# LNA_copy.net
KiCad netlist of a schematic drawn in EAGLE
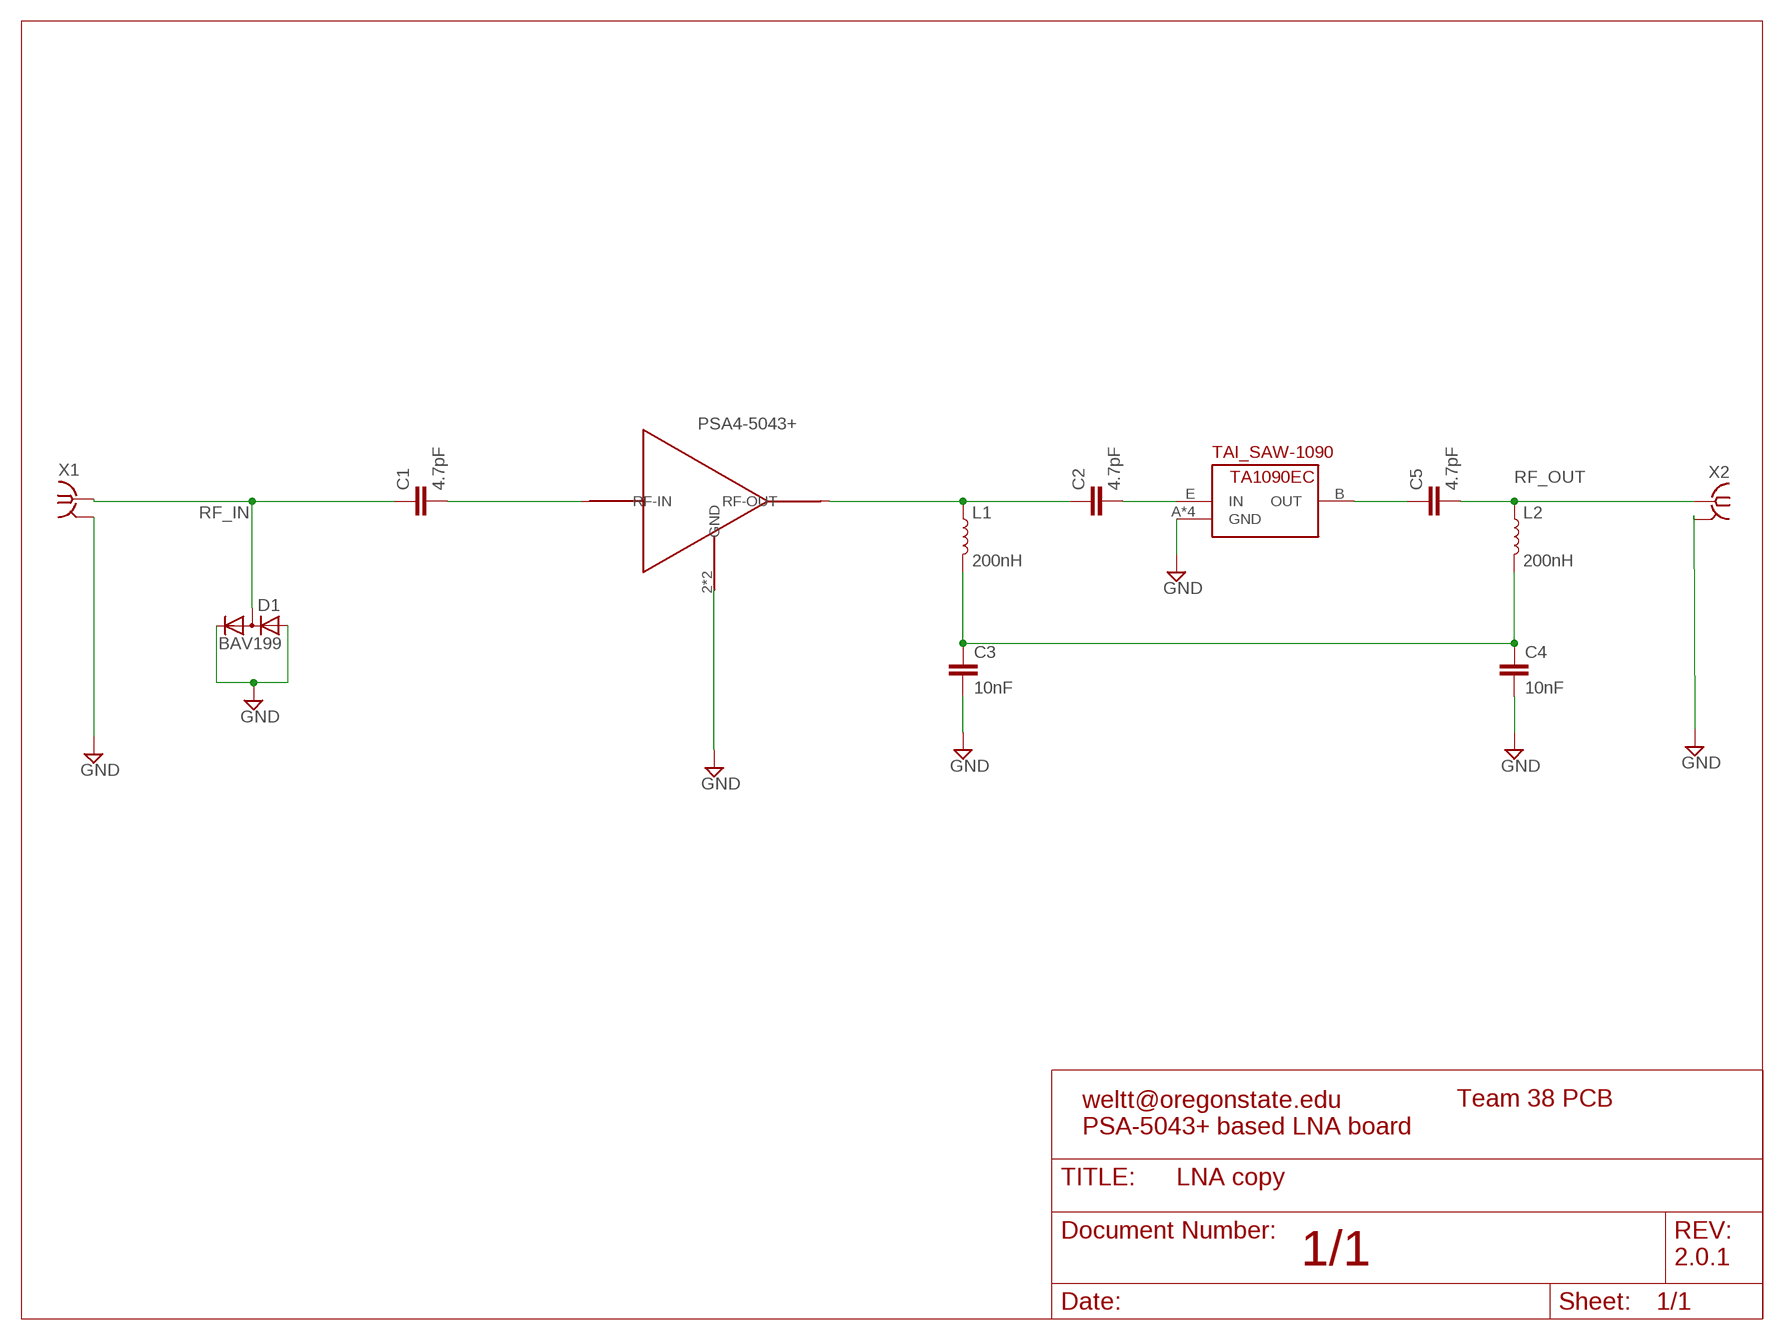
[diagram p0: schematic, sheet 1]

(export (version "E")
  (design (tool "Eeschema 10.0.6"))
  (components
    (comp (ref "C1")
      (value "4.7pF")
      (footprint "eagle-import:C0402")
      (libsource (lib "eagle-import") (part "C-EUC0402"))
    )
    (comp (ref "C2")
      (value "4.7pF")
      (footprint "eagle-import:C0402")
      (libsource (lib "eagle-import") (part "C-EUC0402"))
    )
    (comp (ref "C3")
      (value "10nF")
      (footprint "eagle-import:C0402")
      (libsource (lib "eagle-import") (part "C-EUC0402"))
    )
    (comp (ref "C4")
      (value "10nF")
      (footprint "eagle-import:C0402")
      (libsource (lib "eagle-import") (part "C-EUC0402"))
    )
    (comp (ref "C5")
      (value "4.7pF")
      (footprint "eagle-import:C0402")
      (libsource (lib "eagle-import") (part "C-EUC0402"))
    )
    (comp (ref "D1")
      (value "BAV199")
      (footprint "eagle-import:SOT23")
      (libsource (lib "eagle-import") (part "BAV199"))
    )
    (comp (ref "L1")
      (value "200nH")
      (footprint "eagle-import:0603")
      (libsource (lib "eagle-import") (part "INDUCTOR-0603-33NH"))
    )
    (comp (ref "L2")
      (value "200nH")
      (footprint "eagle-import:0603")
      (libsource (lib "eagle-import") (part "INDUCTOR-0603-33NH"))
    )
    (comp (ref "PSA$-5043")
      (value "PSA4-5043+")
      (footprint "eagle-import:PSA4-5043+")
      (fields
        (field (name "MF") "Mini-Circuits")
        (field (name "MP") "PSA4-5043+")
        (field (name "PACKAGE") "MMM1362")
        (field (name "PRICE") "2.50")
        (field (name "SPICEPREFIX") "M")
      )
      (libsource (lib "eagle-import") (part "PSA4-5043+"))
    )
    (comp (ref "U$1")
      (value "TA1090EC")
      (footprint "eagle-import:TA1090EC")
      (libsource (lib "eagle-import") (part "TA1090EC"))
    )
    (comp (ref "X1")
      (value "SMA-142-0701-801/806")
      (footprint "eagle-import:J502-ND-142-0701-801_806")
      (fields (field (name "MF") "JOHNSON COMPONENTS") (field (name "MPN") "142-0701-801"))
      (libsource (lib "eagle-import") (part "SMA-142-0701-801/806"))
    )
    (comp (ref "X2")
      (value "SMA-142-0701-801/806")
      (footprint "eagle-import:J502-ND-142-0701-801_806")
      (fields (field (name "MF") "JOHNSON COMPONENTS") (field (name "MPN") "142-0701-801"))
      (libsource (lib "eagle-import") (part "SMA-142-0701-801/806"))
    )
  )
  (nets
    (net (code "1") (name "/RF_IN") (class "Default")
      (node (ref "C1") (pin "1") (pinfunction "1_1") (pintype "passive"))
      (node (ref "D1") (pin "3") (pinfunction "AC_3") (pintype "passive"))
      (node (ref "X1") (pin "1") (pinfunction "1_1") (pintype "passive"))
    )
    (net (code "2") (name "/RF_OUT") (class "Default")
      (node (ref "C5") (pin "2") (pinfunction "2_2") (pintype "passive"))
      (node (ref "L2") (pin "1") (pinfunction "1_1") (pintype "passive"))
      (node (ref "X2") (pin "1") (pinfunction "1_1") (pintype "passive"))
    )
    (net (code "3") (name "GND") (class "Default")
      (node (ref "C3") (pin "2") (pinfunction "2_2") (pintype "passive"))
      (node (ref "C4") (pin "2") (pinfunction "2_2") (pintype "passive"))
      (node (ref "D1") (pin "1") (pinfunction "A_1") (pintype "passive"))
      (node (ref "D1") (pin "2") (pinfunction "C_2") (pintype "passive"))
      (node (ref "PSA$-5043") (pin "2") (pinfunction "GND_2") (pintype "bidirectional"))
      (node (ref "PSA$-5043") (pin "4") (pinfunction "GND_4") (pintype "bidirectional"))
      (node (ref "U$1") (pin "A") (pinfunction "GND_A") (pintype "bidirectional"))
      (node (ref "U$1") (pin "C") (pinfunction "GND_C") (pintype "bidirectional"))
      (node (ref "U$1") (pin "D") (pinfunction "GND_D") (pintype "bidirectional"))
      (node (ref "U$1") (pin "F") (pinfunction "GND_F") (pintype "bidirectional"))
      (node (ref "X1") (pin "G@1") (pinfunction "2_G@1") (pintype "passive"))
      (node (ref "X1") (pin "G@2") (pinfunction "2_G@2") (pintype "passive"))
      (node (ref "X1") (pin "G@3") (pinfunction "2_G@3") (pintype "passive"))
      (node (ref "X1") (pin "G@4") (pinfunction "2_G@4") (pintype "passive"))
      (node (ref "X2") (pin "G@1") (pinfunction "2_G@1") (pintype "passive"))
      (node (ref "X2") (pin "G@2") (pinfunction "2_G@2") (pintype "passive"))
      (node (ref "X2") (pin "G@3") (pinfunction "2_G@3") (pintype "passive"))
      (node (ref "X2") (pin "G@4") (pinfunction "2_G@4") (pintype "passive"))
    )
    (net (code "4") (name "Net-(C3-Pad1)") (class "Default")
      (node (ref "C3") (pin "1") (pinfunction "1_1") (pintype "passive"))
      (node (ref "C4") (pin "1") (pinfunction "1_1") (pintype "passive"))
      (node (ref "L1") (pin "2") (pinfunction "2_2") (pintype "passive"))
      (node (ref "L2") (pin "2") (pinfunction "2_2") (pintype "passive"))
    )
    (net (code "5") (name "Net-(PSA$-5043-RF-IN)") (class "Default")
      (node (ref "C1") (pin "2") (pinfunction "2_2") (pintype "passive"))
      (node (ref "PSA$-5043") (pin "3") (pinfunction "RF-IN_3") (pintype "bidirectional"))
    )
    (net (code "6") (name "Net-(PSA$-5043-RF-OUT)") (class "Default")
      (node (ref "C2") (pin "1") (pinfunction "1_1") (pintype "passive"))
      (node (ref "L1") (pin "1") (pinfunction "1_1") (pintype "passive"))
      (node (ref "PSA$-5043") (pin "1") (pinfunction "RF-OUT_1") (pintype "bidirectional"))
    )
    (net (code "7") (name "Net-(U$1-IN)") (class "Default")
      (node (ref "C2") (pin "2") (pinfunction "2_2") (pintype "passive"))
      (node (ref "U$1") (pin "E") (pinfunction "IN_E") (pintype "bidirectional"))
    )
    (net (code "8") (name "Net-(U$1-OUT)") (class "Default")
      (node (ref "C5") (pin "1") (pinfunction "1_1") (pintype "passive"))
      (node (ref "U$1") (pin "B") (pinfunction "OUT_B") (pintype "bidirectional"))
    )
  )
)
